# MCP23S17_Breakout.net
KiCad netlist of a schematic drawn in EAGLE
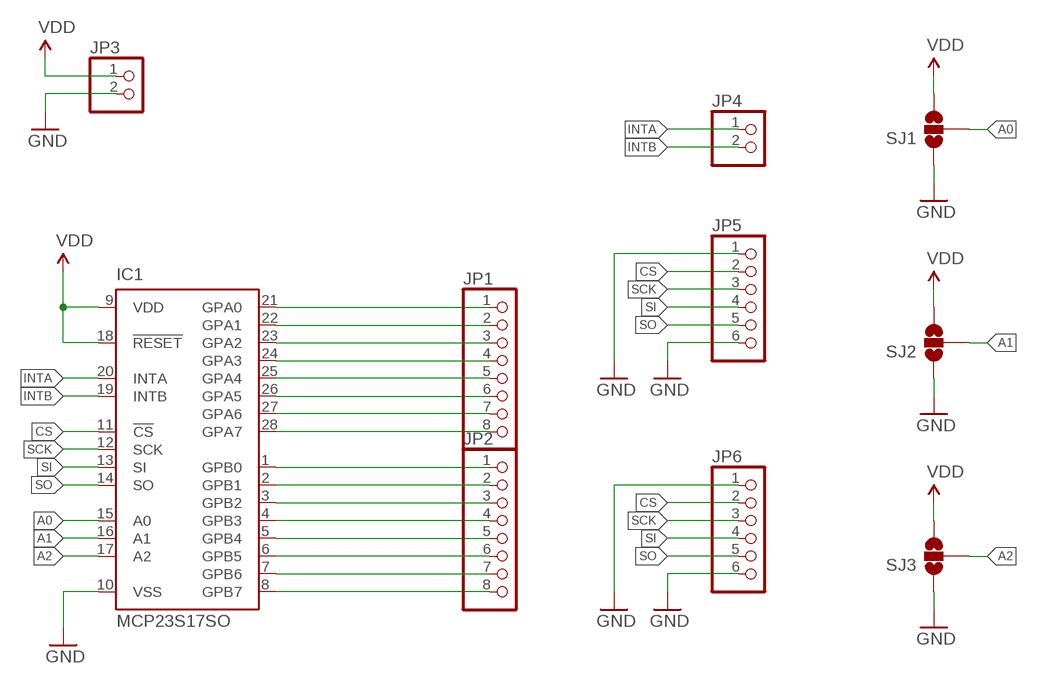
[diagram p0: schematic, sheet 1]

(export (version "E")
  (design (tool "Eeschema 10.0.6"))
  (components
    (comp (ref "IC1")
      (value "MCP23S17SO")
      (footprint "eagle-import:SO28W")
      (fields (field (name "MF") "MICROCHIP") (field (name "MPN") "MCP23S17-E/SO"))
      (libsource (lib "eagle-import") (part "MCP23S17SO"))
    )
    (comp (ref "JP1")
      (value "PINHD-1X8")
      (footprint "eagle-import:1X08")
      (libsource (lib "eagle-import") (part "PINHD-1X8"))
    )
    (comp (ref "JP2")
      (value "PINHD-1X8")
      (footprint "eagle-import:1X08")
      (libsource (lib "eagle-import") (part "PINHD-1X8"))
    )
    (comp (ref "JP3")
      (value "PINHD-1X2")
      (footprint "eagle-import:1X02")
      (libsource (lib "eagle-import") (part "PINHD-1X2"))
    )
    (comp (ref "JP4")
      (value "PINHD-1X2")
      (footprint "eagle-import:1X02")
      (libsource (lib "eagle-import") (part "PINHD-1X2"))
    )
    (comp (ref "JP5")
      (value "PINHD-1X6")
      (footprint "eagle-import:1X06")
      (libsource (lib "eagle-import") (part "PINHD-1X6"))
    )
    (comp (ref "JP6")
      (value "PINHD-1X6")
      (footprint "eagle-import:1X06")
      (libsource (lib "eagle-import") (part "PINHD-1X6"))
    )
    (comp (ref "SJ1")
      (value "SOLDERJUMPER_2WAYT")
      (footprint "eagle-import:SJ_2")
      (libsource (lib "eagle-import") (part "SOLDERJUMPER_2WAYT"))
    )
    (comp (ref "SJ2")
      (value "SOLDERJUMPER_2WAYT")
      (footprint "eagle-import:SJ_2")
      (libsource (lib "eagle-import") (part "SOLDERJUMPER_2WAYT"))
    )
    (comp (ref "SJ3")
      (value "SOLDERJUMPER_2WAYT")
      (footprint "eagle-import:SJ_2")
      (libsource (lib "eagle-import") (part "SOLDERJUMPER_2WAYT"))
    )
  )
  (nets
    (net (code "1") (name "A0") (class "Default")
      (node (ref "IC1") (pin "15") (pinfunction "A0_15") (pintype "input"))
      (node (ref "SJ1") (pin "2") (pinfunction "2_2") (pintype "passive"))
    )
    (net (code "2") (name "A1") (class "Default")
      (node (ref "IC1") (pin "16") (pinfunction "A1_16") (pintype "input"))
      (node (ref "SJ2") (pin "2") (pinfunction "2_2") (pintype "passive"))
    )
    (net (code "3") (name "A2") (class "Default")
      (node (ref "IC1") (pin "17") (pinfunction "A2_17") (pintype "input"))
      (node (ref "SJ3") (pin "2") (pinfunction "2_2") (pintype "passive"))
    )
    (net (code "4") (name "CS") (class "Default")
      (node (ref "IC1") (pin "11") (pinfunction "~{CS}_11") (pintype "input"))
      (node (ref "JP5") (pin "2") (pinfunction "2_2") (pintype "passive"))
      (node (ref "JP6") (pin "2") (pinfunction "2_2") (pintype "passive"))
    )
    (net (code "5") (name "GND") (class "Default")
      (node (ref "IC1") (pin "10") (pinfunction "VSS_10") (pintype "power_in"))
      (node (ref "JP3") (pin "2") (pinfunction "2_2") (pintype "passive"))
      (node (ref "JP5") (pin "1") (pinfunction "1_1") (pintype "passive"))
      (node (ref "JP5") (pin "6") (pinfunction "6_6") (pintype "passive"))
      (node (ref "JP6") (pin "1") (pinfunction "1_1") (pintype "passive"))
      (node (ref "JP6") (pin "6") (pinfunction "6_6") (pintype "passive"))
      (node (ref "SJ1") (pin "1") (pinfunction "1_1") (pintype "passive"))
      (node (ref "SJ2") (pin "1") (pinfunction "1_1") (pintype "passive"))
      (node (ref "SJ3") (pin "1") (pinfunction "1_1") (pintype "passive"))
    )
    (net (code "6") (name "INTA") (class "Default")
      (node (ref "IC1") (pin "20") (pinfunction "INTA_20") (pintype "output"))
      (node (ref "JP4") (pin "1") (pinfunction "1_1") (pintype "passive"))
    )
    (net (code "7") (name "INTB") (class "Default")
      (node (ref "IC1") (pin "19") (pinfunction "INTB_19") (pintype "output"))
      (node (ref "JP4") (pin "2") (pinfunction "2_2") (pintype "passive"))
    )
    (net (code "8") (name "Net-(IC1-GPA0)") (class "Default")
      (node (ref "IC1") (pin "21") (pinfunction "GPA0_21") (pintype "bidirectional"))
      (node (ref "JP1") (pin "1") (pinfunction "1_1") (pintype "passive"))
    )
    (net (code "9") (name "Net-(IC1-GPA1)") (class "Default")
      (node (ref "IC1") (pin "22") (pinfunction "GPA1_22") (pintype "bidirectional"))
      (node (ref "JP1") (pin "2") (pinfunction "2_2") (pintype "passive"))
    )
    (net (code "10") (name "Net-(IC1-GPA2)") (class "Default")
      (node (ref "IC1") (pin "23") (pinfunction "GPA2_23") (pintype "bidirectional"))
      (node (ref "JP1") (pin "3") (pinfunction "3_3") (pintype "passive"))
    )
    (net (code "11") (name "Net-(IC1-GPA3)") (class "Default")
      (node (ref "IC1") (pin "24") (pinfunction "GPA3_24") (pintype "bidirectional"))
      (node (ref "JP1") (pin "4") (pinfunction "4_4") (pintype "passive"))
    )
    (net (code "12") (name "Net-(IC1-GPA4)") (class "Default")
      (node (ref "IC1") (pin "25") (pinfunction "GPA4_25") (pintype "bidirectional"))
      (node (ref "JP1") (pin "5") (pinfunction "5_5") (pintype "passive"))
    )
    (net (code "13") (name "Net-(IC1-GPA5)") (class "Default")
      (node (ref "IC1") (pin "26") (pinfunction "GPA5_26") (pintype "bidirectional"))
      (node (ref "JP1") (pin "6") (pinfunction "6_6") (pintype "passive"))
    )
    (net (code "14") (name "Net-(IC1-GPA6)") (class "Default")
      (node (ref "IC1") (pin "27") (pinfunction "GPA6_27") (pintype "bidirectional"))
      (node (ref "JP1") (pin "7") (pinfunction "7_7") (pintype "passive"))
    )
    (net (code "15") (name "Net-(IC1-GPA7)") (class "Default")
      (node (ref "IC1") (pin "28") (pinfunction "GPA7_28") (pintype "bidirectional"))
      (node (ref "JP1") (pin "8") (pinfunction "8_8") (pintype "passive"))
    )
    (net (code "16") (name "Net-(IC1-GPB0)") (class "Default")
      (node (ref "IC1") (pin "1") (pinfunction "GPB0_1") (pintype "bidirectional"))
      (node (ref "JP2") (pin "1") (pinfunction "1_1") (pintype "passive"))
    )
    (net (code "17") (name "Net-(IC1-GPB1)") (class "Default")
      (node (ref "IC1") (pin "2") (pinfunction "GPB1_2") (pintype "bidirectional"))
      (node (ref "JP2") (pin "2") (pinfunction "2_2") (pintype "passive"))
    )
    (net (code "18") (name "Net-(IC1-GPB2)") (class "Default")
      (node (ref "IC1") (pin "3") (pinfunction "GPB2_3") (pintype "bidirectional"))
      (node (ref "JP2") (pin "3") (pinfunction "3_3") (pintype "passive"))
    )
    (net (code "19") (name "Net-(IC1-GPB3)") (class "Default")
      (node (ref "IC1") (pin "4") (pinfunction "GPB3_4") (pintype "bidirectional"))
      (node (ref "JP2") (pin "4") (pinfunction "4_4") (pintype "passive"))
    )
    (net (code "20") (name "Net-(IC1-GPB4)") (class "Default")
      (node (ref "IC1") (pin "5") (pinfunction "GPB4_5") (pintype "bidirectional"))
      (node (ref "JP2") (pin "5") (pinfunction "5_5") (pintype "passive"))
    )
    (net (code "21") (name "Net-(IC1-GPB5)") (class "Default")
      (node (ref "IC1") (pin "6") (pinfunction "GPB5_6") (pintype "bidirectional"))
      (node (ref "JP2") (pin "6") (pinfunction "6_6") (pintype "passive"))
    )
    (net (code "22") (name "Net-(IC1-GPB6)") (class "Default")
      (node (ref "IC1") (pin "7") (pinfunction "GPB6_7") (pintype "bidirectional"))
      (node (ref "JP2") (pin "7") (pinfunction "7_7") (pintype "passive"))
    )
    (net (code "23") (name "Net-(IC1-GPB7)") (class "Default")
      (node (ref "IC1") (pin "8") (pinfunction "GPB7_8") (pintype "bidirectional"))
      (node (ref "JP2") (pin "8") (pinfunction "8_8") (pintype "passive"))
    )
    (net (code "24") (name "SCK") (class "Default")
      (node (ref "IC1") (pin "12") (pinfunction "SCK_12") (pintype "input"))
      (node (ref "JP5") (pin "3") (pinfunction "3_3") (pintype "passive"))
      (node (ref "JP6") (pin "3") (pinfunction "3_3") (pintype "passive"))
    )
    (net (code "25") (name "SI") (class "Default")
      (node (ref "IC1") (pin "13") (pinfunction "SI_13") (pintype "input"))
      (node (ref "JP5") (pin "4") (pinfunction "4_4") (pintype "passive"))
      (node (ref "JP6") (pin "4") (pinfunction "4_4") (pintype "passive"))
    )
    (net (code "26") (name "SO") (class "Default")
      (node (ref "IC1") (pin "14") (pinfunction "SO_14") (pintype "output"))
      (node (ref "JP5") (pin "5") (pinfunction "5_5") (pintype "passive"))
      (node (ref "JP6") (pin "5") (pinfunction "5_5") (pintype "passive"))
    )
    (net (code "27") (name "VDD") (class "Default")
      (node (ref "IC1") (pin "18") (pinfunction "~{RESET}_18") (pintype "input"))
      (node (ref "IC1") (pin "9") (pinfunction "VDD_9") (pintype "power_in"))
      (node (ref "JP3") (pin "1") (pinfunction "1_1") (pintype "passive"))
      (node (ref "SJ1") (pin "3") (pinfunction "3_3") (pintype "passive"))
      (node (ref "SJ2") (pin "3") (pinfunction "3_3") (pintype "passive"))
      (node (ref "SJ3") (pin "3") (pinfunction "3_3") (pintype "passive"))
    )
  )
)
